# WatchDog.net
KiCad netlist of a schematic drawn in Altium Designer
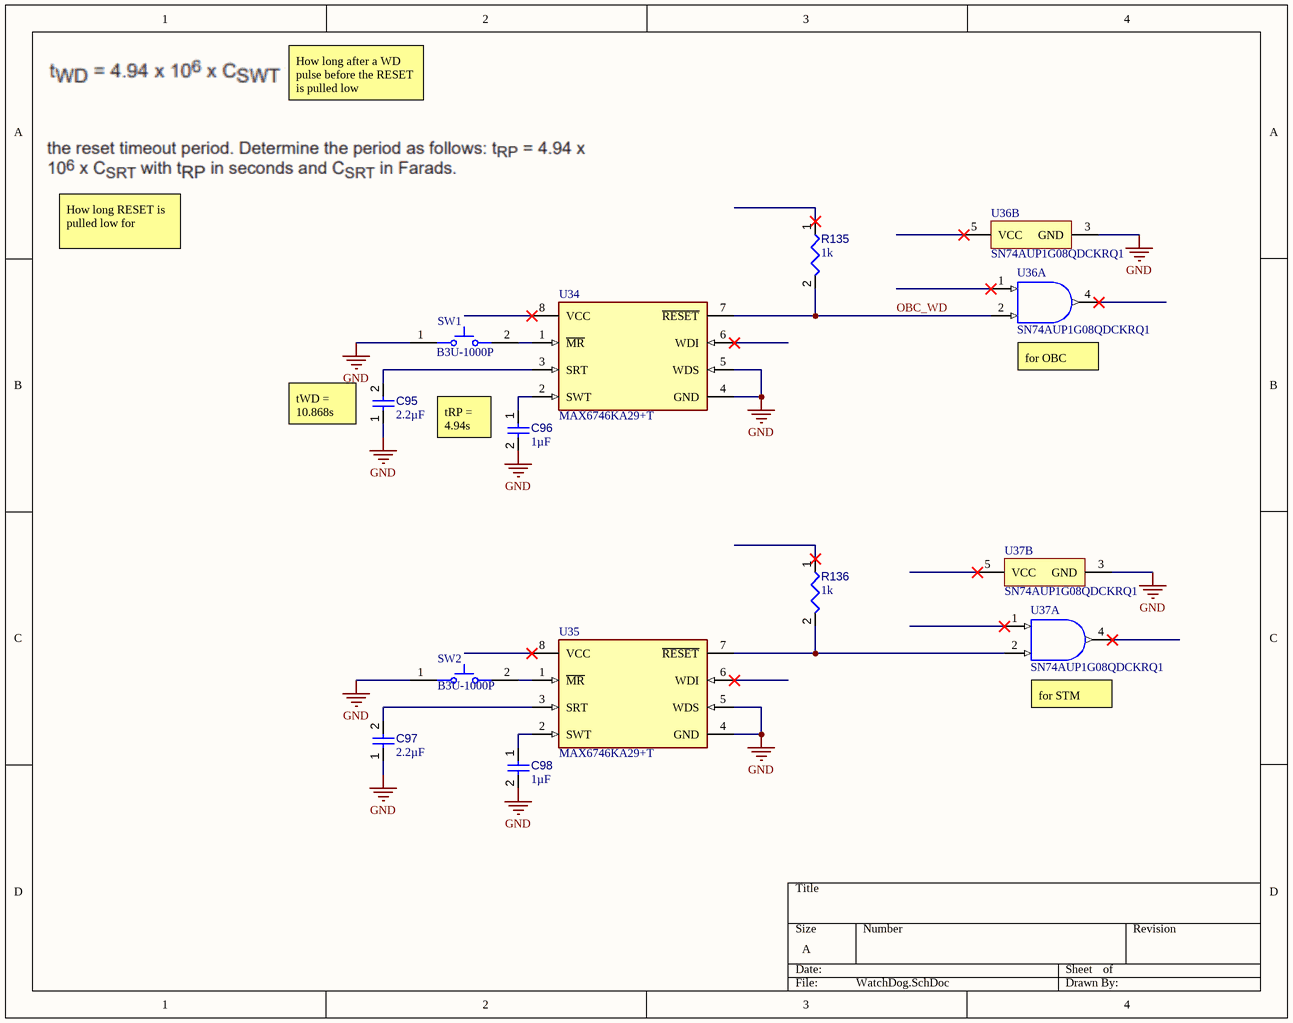
[diagram p0: WatchDog.SchDoc]

(export (version "E")
  (design (tool "Eeschema 10.0.6"))
  (components
    (comp (ref "C95")
      (value "2.2µF")
      (footprint "CAPC0402(1005)60_L")
      (description "Chip Capacitor, 2,2µF +/-20%, 10V, 0402, Thickness 0.6 mm")
      (fields (field (name "TOLERANCE") "10%") (field (name "Comment") "Capacitor 2,2µF +/-20% 10V 0402"))
      (libsource (lib "UGA SSRL Hardware Team") (part "CAP-NP-2"))
    )
    (comp (ref "C96")
      (value "1µF")
      (footprint "CAPC0603(1608)100_L")
      (description "Chip Capacitor, 1µF +/-40%, 50V, 0603, Thickness 1 mm")
      (fields (field (name "TOLERANCE") "10%") (field (name "Comment") "Capacitor 1µF +/-40% 50V 0603"))
      (libsource (lib "UGA SSRL Hardware Team") (part "CAP-NP-2"))
    )
    (comp (ref "C97")
      (value "2.2µF")
      (footprint "CAPC0402(1005)60_L")
      (description "Chip Capacitor, 2,2µF +/-20%, 10V, 0402, Thickness 0.6 mm")
      (fields (field (name "TOLERANCE") "10%") (field (name "Comment") "Capacitor 2,2µF +/-20% 10V 0402"))
      (libsource (lib "UGA SSRL Hardware Team") (part "CAP-NP-2"))
    )
    (comp (ref "C98")
      (value "1µF")
      (footprint "CAPC0603(1608)100_L")
      (description "Chip Capacitor, 1µF +/-40%, 50V, 0603, Thickness 1 mm")
      (fields (field (name "TOLERANCE") "10%") (field (name "Comment") "Capacitor 1µF +/-40% 50V 0603"))
      (libsource (lib "UGA SSRL Hardware Team") (part "CAP-NP-2"))
    )
    (comp (ref "R135")
      (value "1k")
      (footprint "RESC0805(2012)_L")
      (description "1K 0.125W 5% 0805 (2012 Metric)  SMD")
      (fields (field (name "TOLERANCE") "5%") (field (name "POWER") "125mW"))
      (libsource (lib "UGA SSRL Hardware Team") (part "1KR5J"))
    )
    (comp (ref "R136")
      (value "1k")
      (footprint "RESC0805(2012)_L")
      (description "1K 0.125W 5% 0805 (2012 Metric)  SMD")
      (fields (field (name "TOLERANCE") "5%") (field (name "POWER") "125mW"))
      (libsource (lib "UGA SSRL Hardware Team") (part "1KR5J"))
    )
    (comp (ref "SW1")
      (value "B3U-1000P")
      (footprint "OMRON-B3U-1000_V")
      (description "Tactile Switch, SPST-NO, 0.05 A, 12 V, -25 to 70 degC, 2-Pin SMD, RoHS, Tape and Reel")
      (fields (field (name "MANUFACTURER") "Omron Electronic Components"))
      (libsource (lib "UGA SSRL Hardware Team") (part "SW-SPST-NO-2"))
    )
    (comp (ref "SW2")
      (value "B3U-1000P")
      (footprint "OMRON-B3U-1000_V")
      (description "Tactile Switch, SPST-NO, 0.05 A, 12 V, -25 to 70 degC, 2-Pin SMD, RoHS, Tape and Reel")
      (fields (field (name "MANUFACTURER") "Omron Electronic Components"))
      (libsource (lib "UGA SSRL Hardware Team") (part "SW-SPST-NO-2"))
    )
    (comp (ref "U34")
      (value "MAX6746KA29+T")
      (footprint "FP-K8-5-IPC_C")
      (description "Power Supply Management Circuit, Adjustable, 1 Channel, BICMOS, PDSO8")
      (libsource (lib "UGA SSRL Hardware Team") (part "08e5617605ea42384b69bce613a8bab"))
    )
    (comp (ref "U35")
      (value "MAX6746KA29+T")
      (footprint "FP-K8-5-IPC_C")
      (description "Power Supply Management Circuit, Adjustable, 1 Channel, BICMOS, PDSO8")
      (libsource (lib "UGA SSRL Hardware Team") (part "08e5617605ea42384b69bce613a8bab"))
    )
    (comp (ref "U36")
      (value "SN74AUP1G08QDCKRQ1")
      (footprint "DCK0005A_N")
      (description "AND Gate, AUP/ULP/V Series, 1-Func, 2-Input, CMOS, PDSO5")
      (libsource (lib "UGA SSRL Hardware Team") (part "TI-SN74XXX1X08-5"))
    )
    (comp (ref "U37")
      (value "SN74AUP1G08QDCKRQ1")
      (footprint "DCK0005A_N")
      (description "AND Gate, AUP/ULP/V Series, 1-Func, 2-Input, CMOS, PDSO5")
      (libsource (lib "UGA SSRL Hardware Team") (part "TI-SN74XXX1X08-5"))
    )
  )
  (nets
    (net (code "1") (name "/OBC_WD") (class "Default")
      (node (ref "R135") (pin "2") (pinfunction "2_2") (pintype "passive"))
      (node (ref "U34") (pin "7") (pinfunction "~{RESET}_7") (pintype "open_collector"))
      (node (ref "U36") (pin "2") (pinfunction "B_2") (pintype "input"))
    )
    (net (code "2") (name "GND") (class "Default")
      (node (ref "C95") (pin "1") (pinfunction "1_1") (pintype "passive"))
      (node (ref "C96") (pin "2") (pinfunction "2_2") (pintype "passive"))
      (node (ref "C97") (pin "1") (pinfunction "1_1") (pintype "passive"))
      (node (ref "C98") (pin "2") (pinfunction "2_2") (pintype "passive"))
      (node (ref "SW1") (pin "1") (pinfunction "1_1") (pintype "passive"))
      (node (ref "SW2") (pin "1") (pinfunction "1_1") (pintype "passive"))
      (node (ref "U34") (pin "4") (pinfunction "GND_4") (pintype "power_in"))
      (node (ref "U34") (pin "5") (pinfunction "WDS_5") (pintype "input"))
      (node (ref "U35") (pin "4") (pinfunction "GND_4") (pintype "power_in"))
      (node (ref "U35") (pin "5") (pinfunction "WDS_5") (pintype "input"))
      (node (ref "U36") (pin "3") (pinfunction "GND_3") (pintype "power_in"))
      (node (ref "U37") (pin "3") (pinfunction "GND_3") (pintype "power_in"))
    )
    (net (code "3") (name "Net-(U34-SRT)") (class "Default")
      (node (ref "C95") (pin "2") (pinfunction "2_2") (pintype "passive"))
      (node (ref "U34") (pin "3") (pinfunction "SRT_3") (pintype "input"))
    )
    (net (code "4") (name "Net-(U34-SWT)") (class "Default")
      (node (ref "C96") (pin "1") (pinfunction "1_1") (pintype "passive"))
      (node (ref "U34") (pin "2") (pinfunction "SWT_2") (pintype "input"))
    )
    (net (code "5") (name "Net-(U34-~{MR})") (class "Default")
      (node (ref "SW1") (pin "2") (pinfunction "2_2") (pintype "passive"))
      (node (ref "U34") (pin "1") (pinfunction "~{MR}_1") (pintype "input"))
    )
    (net (code "6") (name "Net-(U35-SRT)") (class "Default")
      (node (ref "C97") (pin "2") (pinfunction "2_2") (pintype "passive"))
      (node (ref "U35") (pin "3") (pinfunction "SRT_3") (pintype "input"))
    )
    (net (code "7") (name "Net-(U35-SWT)") (class "Default")
      (node (ref "C98") (pin "1") (pinfunction "1_1") (pintype "passive"))
      (node (ref "U35") (pin "2") (pinfunction "SWT_2") (pintype "input"))
    )
    (net (code "8") (name "Net-(U35-~{MR})") (class "Default")
      (node (ref "SW2") (pin "2") (pinfunction "2_2") (pintype "passive"))
      (node (ref "U35") (pin "1") (pinfunction "~{MR}_1") (pintype "input"))
    )
    (net (code "9") (name "Net-(U35-~{RESET})") (class "Default")
      (node (ref "R136") (pin "2") (pinfunction "2_2") (pintype "passive"))
      (node (ref "U35") (pin "7") (pinfunction "~{RESET}_7") (pintype "open_collector"))
      (node (ref "U37") (pin "2") (pinfunction "B_2") (pintype "input"))
    )
    (net (code "10") (name "unconnected-(R135-Pad1)") (class "Default")
      (node (ref "R135") (pin "1") (pinfunction "1_1") (pintype "passive+no_connect"))
    )
    (net (code "11") (name "unconnected-(R136-Pad1)") (class "Default")
      (node (ref "R136") (pin "1") (pinfunction "1_1") (pintype "passive+no_connect"))
    )
    (net (code "12") (name "unconnected-(U34-VCC-Pad8)") (class "Default")
      (node (ref "U34") (pin "8") (pinfunction "VCC_8") (pintype "power_in+no_connect"))
    )
    (net (code "13") (name "unconnected-(U34-WDI-Pad6)") (class "Default")
      (node (ref "U34") (pin "6") (pinfunction "WDI_6") (pintype "input+no_connect"))
    )
    (net (code "14") (name "unconnected-(U35-VCC-Pad8)") (class "Default")
      (node (ref "U35") (pin "8") (pinfunction "VCC_8") (pintype "power_in+no_connect"))
    )
    (net (code "15") (name "unconnected-(U35-WDI-Pad6)") (class "Default")
      (node (ref "U35") (pin "6") (pinfunction "WDI_6") (pintype "input+no_connect"))
    )
    (net (code "16") (name "unconnected-(U36A-A-Pad1)") (class "Default")
      (node (ref "U36") (pin "1") (pinfunction "A_1") (pintype "input+no_connect"))
    )
    (net (code "17") (name "unconnected-(U36A-Y-Pad4)") (class "Default")
      (node (ref "U36") (pin "4") (pinfunction "Y_4") (pintype "output+no_connect"))
    )
    (net (code "18") (name "unconnected-(U36B-VCC-Pad5)") (class "Default")
      (node (ref "U36") (pin "5") (pinfunction "VCC_5") (pintype "power_in+no_connect"))
    )
    (net (code "19") (name "unconnected-(U37A-A-Pad1)") (class "Default")
      (node (ref "U37") (pin "1") (pinfunction "A_1") (pintype "input+no_connect"))
    )
    (net (code "20") (name "unconnected-(U37A-Y-Pad4)") (class "Default")
      (node (ref "U37") (pin "4") (pinfunction "Y_4") (pintype "output+no_connect"))
    )
    (net (code "21") (name "unconnected-(U37B-VCC-Pad5)") (class "Default")
      (node (ref "U37") (pin "5") (pinfunction "VCC_5") (pintype "power_in+no_connect"))
    )
  )
)
